# REALcontrol_boardv22.net
KiCad netlist of a schematic drawn in EAGLE
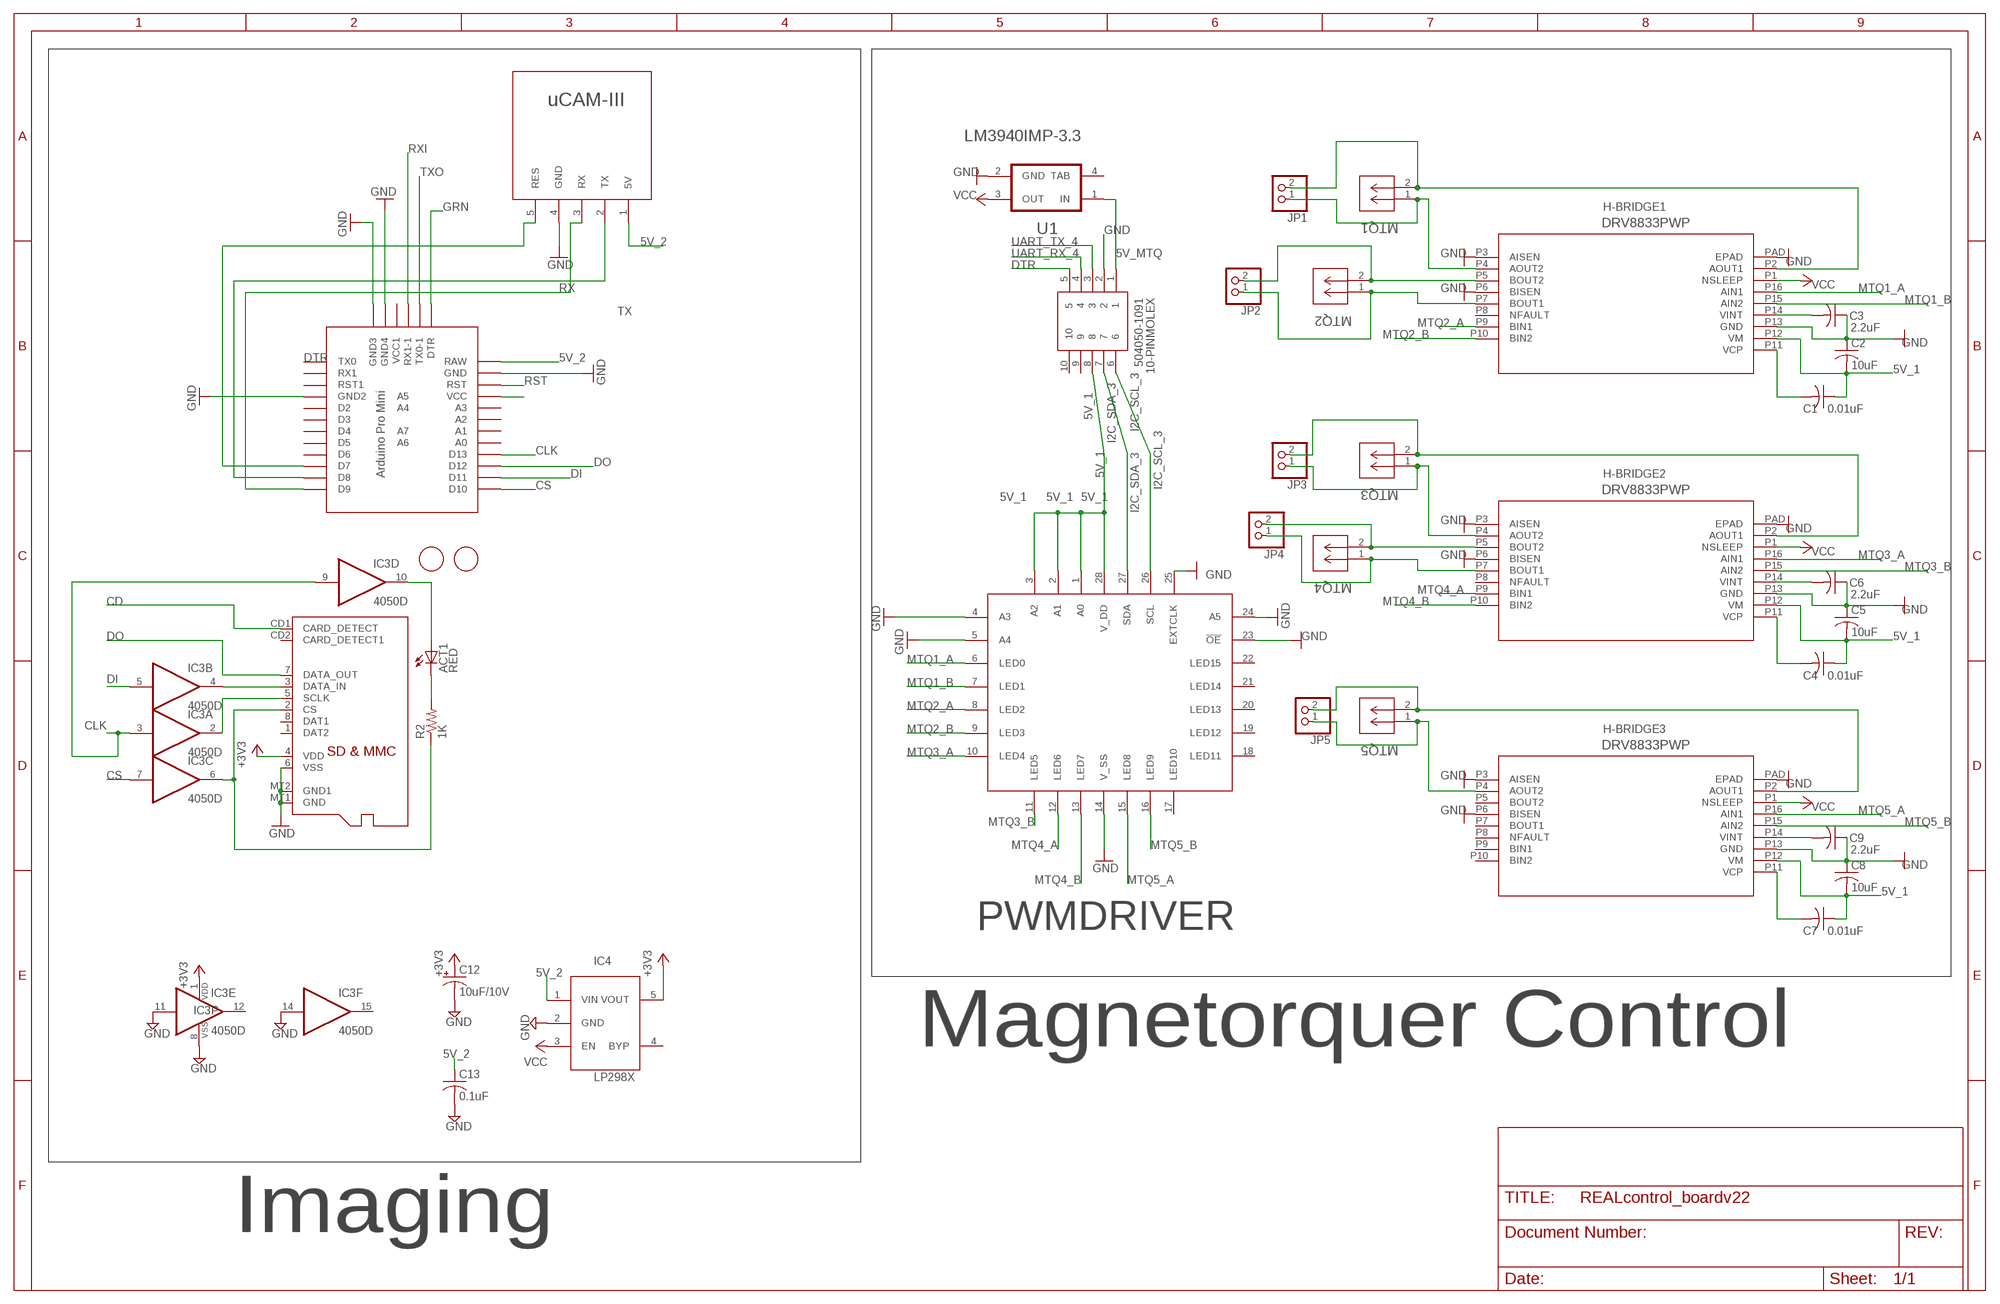
[diagram p0: schematic, sheet 1]

(export (version "E")
  (design (tool "Eeschema 10.0.6"))
  (components
    (comp (ref "10-PINMOLEX")
      (value "504050-1091")
      (footprint "eagle-import:504050-1091")
      (fields (field (name "MOUSER_PART_NUMBER") "538-504050-1091"))
      (libsource (lib "eagle-import") (part "504050-1091"))
    )
    (comp (ref "ACT1")
      (value "RED")
      (footprint "eagle-import:CHIP-LED0805")
      (libsource (lib "eagle-import") (part "LEDCHIP-LED0805"))
    )
    (comp (ref "C1")
      (value "0.01uF")
      (footprint "eagle-import:C0603K")
      (libsource (lib "eagle-import") (part "rcl_334_C-USC0603K"))
    )
    (comp (ref "C2")
      (value "10uF")
      (footprint "eagle-import:C1210K")
      (libsource (lib "eagle-import") (part "rcl_334_C-USC1210K"))
    )
    (comp (ref "C3")
      (value "2.2uF")
      (footprint "eagle-import:C0603K")
      (libsource (lib "eagle-import") (part "rcl_334_C-USC0603K"))
    )
    (comp (ref "C4")
      (value "0.01uF")
      (footprint "eagle-import:C0603K")
      (libsource (lib "eagle-import") (part "rcl_334_C-USC0603K"))
    )
    (comp (ref "C5")
      (value "10uF")
      (footprint "eagle-import:C1210K")
      (libsource (lib "eagle-import") (part "rcl_334_C-USC1210K"))
    )
    (comp (ref "C6")
      (value "2.2uF")
      (footprint "eagle-import:C0603K")
      (libsource (lib "eagle-import") (part "rcl_334_C-USC0603K"))
    )
    (comp (ref "C7")
      (value "0.01uF")
      (footprint "eagle-import:C0603K")
      (libsource (lib "eagle-import") (part "rcl_334_C-USC0603K"))
    )
    (comp (ref "C8")
      (value "10uF")
      (footprint "eagle-import:C1210K")
      (libsource (lib "eagle-import") (part "rcl_334_C-USC1210K"))
    )
    (comp (ref "C9")
      (value "2.2uF")
      (footprint "eagle-import:C0603K")
      (libsource (lib "eagle-import") (part "rcl_334_C-USC0603K"))
    )
    (comp (ref "C12")
      (value "10uF/10V")
      (footprint "eagle-import:A_3216-18R")
      (libsource (lib "eagle-import") (part "CPOL-USA/3216-18R"))
    )
    (comp (ref "C13")
      (value "0.1uF")
      (footprint "eagle-import:C0805K")
      (libsource (lib "eagle-import") (part "C-USC0805K"))
    )
    (comp (ref "H-BRIDGE1")
      (value "DRV8833PWP")
      (footprint "eagle-import:HTSSOP16")
      (libsource (lib "eagle-import") (part "DRV8833PWP"))
    )
    (comp (ref "H-BRIDGE2")
      (value "DRV8833PWP")
      (footprint "eagle-import:HTSSOP16")
      (libsource (lib "eagle-import") (part "DRV8833PWP"))
    )
    (comp (ref "H-BRIDGE3")
      (value "DRV8833PWP")
      (footprint "eagle-import:HTSSOP16")
      (libsource (lib "eagle-import") (part "DRV8833PWP"))
    )
    (comp (ref "IC3")
      (value "4050D")
      (footprint "eagle-import:SO16")
      (fields (field (name "OC_NEWARK") "unknown"))
      (libsource (lib "eagle-import") (part "4050D"))
    )
    (comp (ref "IC4")
      (value "LP298XS")
      (footprint "eagle-import:SOT23-5L")
      (libsource (lib "eagle-import") (part "LP298XS"))
    )
    (comp (ref "JP1")
      (value "PINHD-1X2")
      (footprint "eagle-import:1X02")
      (fields (field (name "MF") "MOLEX") (field (name "MPN") "22-11-2022"))
      (libsource (lib "eagle-import") (part "PINHD-1X2"))
    )
    (comp (ref "JP2")
      (value "PINHD-1X2")
      (footprint "eagle-import:1X02")
      (fields (field (name "MF") "MOLEX") (field (name "MPN") "22-11-2022"))
      (libsource (lib "eagle-import") (part "PINHD-1X2"))
    )
    (comp (ref "JP3")
      (value "PINHD-1X2")
      (footprint "eagle-import:1X02")
      (fields (field (name "MF") "MOLEX") (field (name "MPN") "22-11-2022"))
      (libsource (lib "eagle-import") (part "PINHD-1X2"))
    )
    (comp (ref "JP4")
      (value "PINHD-1X2")
      (footprint "eagle-import:1X02")
      (fields (field (name "MF") "MOLEX") (field (name "MPN") "22-11-2022"))
      (libsource (lib "eagle-import") (part "PINHD-1X2"))
    )
    (comp (ref "JP5")
      (value "PINHD-1X2")
      (footprint "eagle-import:1X02")
      (fields (field (name "MF") "MOLEX") (field (name "MPN") "22-11-2022"))
      (libsource (lib "eagle-import") (part "PINHD-1X2"))
    )
    (comp (ref "MTQ1")
      (value "DF13C-2P-1.25V(51)")
      (footprint "eagle-import:CON2_1X2_U_DF13")
      (libsource (lib "eagle-import") (part "DF13C-2P-1.25V(51)"))
    )
    (comp (ref "MTQ2")
      (value "DF13C-2P-1.25V(51)")
      (footprint "eagle-import:CON2_1X2_U_DF13")
      (libsource (lib "eagle-import") (part "DF13C-2P-1.25V(51)"))
    )
    (comp (ref "MTQ3")
      (value "DF13C-2P-1.25V(51)")
      (footprint "eagle-import:CON2_1X2_U_DF13")
      (libsource (lib "eagle-import") (part "DF13C-2P-1.25V(51)"))
    )
    (comp (ref "MTQ4")
      (value "DF13C-2P-1.25V(51)")
      (footprint "eagle-import:CON2_1X2_U_DF13")
      (libsource (lib "eagle-import") (part "DF13C-2P-1.25V(51)"))
    )
    (comp (ref "MTQ5")
      (value "DF13C-2P-1.25V(51)")
      (footprint "eagle-import:CON2_1X2_U_DF13")
      (libsource (lib "eagle-import") (part "DF13C-2P-1.25V(51)"))
    )
    (comp (ref "PWMDRIVER")
      (value "PCA9685PW")
      (footprint "eagle-import:TSSOP28")
      (libsource (lib "eagle-import") (part "PCA9685PW"))
    )
    (comp (ref "R2")
      (value "1K")
      (footprint "eagle-import:R0805")
      (libsource (lib "eagle-import") (part "R-US_R0805"))
    )
    (comp (ref "U$2")
      (value "UCAM-III")
      (footprint "eagle-import:UCAM-III")
      (libsource (lib "eagle-import") (part "UCAM-III"))
    )
    (comp (ref "U$6")
      (value "FIDUCIAL")
      (footprint "eagle-import:FIDUCIAL_1MM")
      (libsource (lib "eagle-import") (part "FIDUCIAL"))
    )
    (comp (ref "U$7")
      (value "FIDUCIAL")
      (footprint "eagle-import:FIDUCIAL_1MM")
      (libsource (lib "eagle-import") (part "FIDUCIAL"))
    )
    (comp (ref "U$8")
      (value "PRO-MINI-2")
      (footprint "eagle-import:PRO-MINI-2")
      (libsource (lib "eagle-import") (part "PRO-MINI-2"))
    )
    (comp (ref "U1")
      (value "TI_NATIONAL_SEMICONDUCTOR_LM3940IMP-3.3TI_NATIONAL_SEMICONDUCTOR_LM3940IMP-3.3_0_1")
      (footprint "eagle-import:TI_NATIONAL_SEMICONDUCTOR_LM3940IMP-3.3_1")
      (fields (field (name "MF") "TI National Semiconductor") (field (name "MPN") "LM3940IMP-3.3"))
      (libsource (lib "eagle-import") (part "TI_NATIONAL_SEMICONDUCTOR_LM3940IMP-3.3TI_NATIONAL_SEMICONDUCTOR_LM3940IMP-3.3_0_1"))
    )
    (comp (ref "X2")
      (value "MICROSD")
      (footprint "eagle-import:MICROSD")
      (libsource (lib "eagle-import") (part "MICROSD"))
    )
  )
  (nets
    (net (code "1") (name "+3V3") (class "Default")
      (node (ref "C12") (pin "+") (pinfunction "+_+") (pintype "passive"))
      (node (ref "IC3") (pin "1") (pinfunction "VDD_1") (pintype "power_in"))
      (node (ref "IC4") (pin "5") (pinfunction "VOUT_5") (pintype "bidirectional"))
      (node (ref "X2") (pin "4") (pinfunction "VDD_4") (pintype "power_in"))
    )
    (net (code "2") (name "/5V_1") (class "Default")
      (node (ref "10-PINMOLEX") (pin "8") (pinfunction "8_8") (pintype "bidirectional"))
      (node (ref "C1") (pin "1") (pinfunction "1_1") (pintype "passive"))
      (node (ref "C2") (pin "2") (pinfunction "2_2") (pintype "passive"))
      (node (ref "C4") (pin "1") (pinfunction "1_1") (pintype "passive"))
      (node (ref "C5") (pin "2") (pinfunction "2_2") (pintype "passive"))
      (node (ref "C7") (pin "1") (pinfunction "1_1") (pintype "passive"))
      (node (ref "C8") (pin "2") (pinfunction "2_2") (pintype "passive"))
      (node (ref "H-BRIDGE1") (pin "P12") (pinfunction "VM_P12") (pintype "power_in"))
      (node (ref "H-BRIDGE2") (pin "P12") (pinfunction "VM_P12") (pintype "power_in"))
      (node (ref "H-BRIDGE3") (pin "P12") (pinfunction "VM_P12") (pintype "power_in"))
      (node (ref "PWMDRIVER") (pin "1") (pinfunction "A0_1") (pintype "bidirectional"))
      (node (ref "PWMDRIVER") (pin "2") (pinfunction "A1_2") (pintype "bidirectional"))
      (node (ref "PWMDRIVER") (pin "28") (pinfunction "V_DD_28") (pintype "bidirectional"))
      (node (ref "PWMDRIVER") (pin "3") (pinfunction "A2_3") (pintype "bidirectional"))
    )
    (net (code "3") (name "/5V_2") (class "Default")
      (node (ref "C13") (pin "1") (pinfunction "1_1") (pintype "passive"))
      (node (ref "IC4") (pin "1") (pinfunction "VIN_1") (pintype "bidirectional"))
      (node (ref "U$2") (pin "1") (pinfunction "5V_1") (pintype "bidirectional"))
      (node (ref "U$8") (pin "RAW") (pinfunction "RAW_RAW") (pintype "bidirectional"))
    )
    (net (code "4") (name "/5V_MTQ") (class "Default")
      (node (ref "10-PINMOLEX") (pin "1") (pinfunction "1_1") (pintype "bidirectional"))
      (node (ref "U1") (pin "1") (pinfunction "IN_1") (pintype "power_in"))
    )
    (net (code "5") (name "/CD") (class "Default")
      (node (ref "X2") (pin "CD1") (pinfunction "CARD_DETECT_CD1") (pintype "passive"))
    )
    (net (code "6") (name "/CLK") (class "Default")
      (node (ref "IC3") (pin "3") (pinfunction "I_3") (pintype "input"))
      (node (ref "IC3") (pin "9") (pinfunction "I_9") (pintype "input"))
      (node (ref "U$8") (pin "D13") (pinfunction "D13_D13") (pintype "bidirectional"))
    )
    (net (code "7") (name "/CS") (class "Default")
      (node (ref "IC3") (pin "7") (pinfunction "I_7") (pintype "input"))
      (node (ref "U$8") (pin "D10") (pinfunction "D10_D10") (pintype "bidirectional"))
    )
    (net (code "8") (name "/DI") (class "Default")
      (node (ref "IC3") (pin "5") (pinfunction "I_5") (pintype "input"))
      (node (ref "U$8") (pin "D11") (pinfunction "D11_D11") (pintype "bidirectional"))
    )
    (net (code "9") (name "/DO") (class "Default")
      (node (ref "U$8") (pin "D12") (pinfunction "D12_D12") (pintype "bidirectional"))
      (node (ref "X2") (pin "7") (pinfunction "DATA_OUT_7") (pintype "output"))
    )
    (net (code "10") (name "/DTR") (class "Default")
      (node (ref "10-PINMOLEX") (pin "5") (pinfunction "5_5") (pintype "bidirectional"))
    )
    (net (code "11") (name "/GRN") (class "Default")
      (node (ref "U$8") (pin "DTR") (pinfunction "DTR_DTR") (pintype "bidirectional"))
    )
    (net (code "12") (name "/I2C_SCL_3") (class "Default")
      (node (ref "10-PINMOLEX") (pin "6") (pinfunction "6_6") (pintype "bidirectional"))
      (node (ref "PWMDRIVER") (pin "26") (pinfunction "SCL_26") (pintype "bidirectional"))
    )
    (net (code "13") (name "/I2C_SDA_3") (class "Default")
      (node (ref "10-PINMOLEX") (pin "7") (pinfunction "7_7") (pintype "bidirectional"))
      (node (ref "PWMDRIVER") (pin "27") (pinfunction "SDA_27") (pintype "bidirectional"))
    )
    (net (code "14") (name "/MTQ1_A") (class "Default")
      (node (ref "H-BRIDGE1") (pin "P16") (pinfunction "AIN1_P16") (pintype "input"))
      (node (ref "PWMDRIVER") (pin "6") (pinfunction "LED0_6") (pintype "bidirectional"))
    )
    (net (code "15") (name "/MTQ1_B") (class "Default")
      (node (ref "H-BRIDGE1") (pin "P15") (pinfunction "AIN2_P15") (pintype "input"))
      (node (ref "PWMDRIVER") (pin "7") (pinfunction "LED1_7") (pintype "bidirectional"))
    )
    (net (code "16") (name "/MTQ2_A") (class "Default")
      (node (ref "H-BRIDGE1") (pin "P9") (pinfunction "BIN1_P9") (pintype "input"))
      (node (ref "PWMDRIVER") (pin "8") (pinfunction "LED2_8") (pintype "bidirectional"))
    )
    (net (code "17") (name "/MTQ2_B") (class "Default")
      (node (ref "H-BRIDGE1") (pin "P10") (pinfunction "BIN2_P10") (pintype "input"))
      (node (ref "PWMDRIVER") (pin "9") (pinfunction "LED3_9") (pintype "bidirectional"))
    )
    (net (code "18") (name "/MTQ3_A") (class "Default")
      (node (ref "H-BRIDGE2") (pin "P16") (pinfunction "AIN1_P16") (pintype "input"))
      (node (ref "PWMDRIVER") (pin "10") (pinfunction "LED4_10") (pintype "bidirectional"))
    )
    (net (code "19") (name "/MTQ3_B") (class "Default")
      (node (ref "H-BRIDGE2") (pin "P15") (pinfunction "AIN2_P15") (pintype "input"))
      (node (ref "PWMDRIVER") (pin "11") (pinfunction "LED5_11") (pintype "bidirectional"))
    )
    (net (code "20") (name "/MTQ4_A") (class "Default")
      (node (ref "H-BRIDGE2") (pin "P9") (pinfunction "BIN1_P9") (pintype "input"))
      (node (ref "PWMDRIVER") (pin "12") (pinfunction "LED6_12") (pintype "bidirectional"))
    )
    (net (code "21") (name "/MTQ4_B") (class "Default")
      (node (ref "H-BRIDGE2") (pin "P10") (pinfunction "BIN2_P10") (pintype "input"))
      (node (ref "PWMDRIVER") (pin "13") (pinfunction "LED7_13") (pintype "bidirectional"))
    )
    (net (code "22") (name "/MTQ5_A") (class "Default")
      (node (ref "H-BRIDGE3") (pin "P16") (pinfunction "AIN1_P16") (pintype "input"))
      (node (ref "PWMDRIVER") (pin "15") (pinfunction "LED8_15") (pintype "bidirectional"))
    )
    (net (code "23") (name "/MTQ5_B") (class "Default")
      (node (ref "H-BRIDGE3") (pin "P15") (pinfunction "AIN2_P15") (pintype "input"))
      (node (ref "PWMDRIVER") (pin "16") (pinfunction "LED9_16") (pintype "bidirectional"))
    )
    (net (code "24") (name "/RST") (class "Default")
      (node (ref "U$8") (pin "RST") (pinfunction "RST_RST") (pintype "bidirectional"))
    )
    (net (code "25") (name "/RX") (class "Default")
      (node (ref "U$2") (pin "3") (pinfunction "RX_3") (pintype "bidirectional"))
      (node (ref "U$8") (pin "D9") (pinfunction "D9_D9") (pintype "bidirectional"))
    )
    (net (code "26") (name "/RXI") (class "Default")
      (node (ref "U$8") (pin "RX1-1") (pinfunction "RX1-1_RX1-1") (pintype "bidirectional"))
    )
    (net (code "27") (name "/TAB") (class "Default")
      (node (ref "U1") (pin "4") (pinfunction "TAB_4") (pintype "power_in"))
    )
    (net (code "28") (name "/TX") (class "Default")
      (node (ref "U$2") (pin "2") (pinfunction "TX_2") (pintype "bidirectional"))
      (node (ref "U$8") (pin "D8") (pinfunction "D8_D8") (pintype "bidirectional"))
    )
    (net (code "29") (name "/TXO") (class "Default")
      (node (ref "U$8") (pin "TX0-1") (pinfunction "TX0-1_TX0-1") (pintype "bidirectional"))
    )
    (net (code "30") (name "/UART_RX_4") (class "Default")
      (node (ref "10-PINMOLEX") (pin "4") (pinfunction "4_4") (pintype "bidirectional"))
    )
    (net (code "31") (name "/UART_TX_4") (class "Default")
      (node (ref "10-PINMOLEX") (pin "3") (pinfunction "3_3") (pintype "bidirectional"))
    )
    (net (code "32") (name "GND") (class "Default")
      (node (ref "10-PINMOLEX") (pin "2") (pinfunction "2_2") (pintype "bidirectional"))
      (node (ref "C12") (pin "-") (pinfunction "-_-") (pintype "passive"))
      (node (ref "C13") (pin "2") (pinfunction "2_2") (pintype "passive"))
      (node (ref "C2") (pin "1") (pinfunction "1_1") (pintype "passive"))
      (node (ref "C3") (pin "1") (pinfunction "1_1") (pintype "passive"))
      (node (ref "C5") (pin "1") (pinfunction "1_1") (pintype "passive"))
      (node (ref "C6") (pin "1") (pinfunction "1_1") (pintype "passive"))
      (node (ref "C8") (pin "1") (pinfunction "1_1") (pintype "passive"))
      (node (ref "C9") (pin "1") (pinfunction "1_1") (pintype "passive"))
      (node (ref "H-BRIDGE1") (pin "P13") (pinfunction "GND_P13") (pintype "power_in"))
      (node (ref "H-BRIDGE1") (pin "P3") (pinfunction "AISEN_P3") (pintype "bidirectional"))
      (node (ref "H-BRIDGE1") (pin "P6") (pinfunction "BISEN_P6") (pintype "bidirectional"))
      (node (ref "H-BRIDGE1") (pin "PAD") (pinfunction "EPAD_PAD") (pintype "passive"))
      (node (ref "H-BRIDGE2") (pin "P13") (pinfunction "GND_P13") (pintype "power_in"))
      (node (ref "H-BRIDGE2") (pin "P3") (pinfunction "AISEN_P3") (pintype "bidirectional"))
      (node (ref "H-BRIDGE2") (pin "P6") (pinfunction "BISEN_P6") (pintype "bidirectional"))
      (node (ref "H-BRIDGE2") (pin "PAD") (pinfunction "EPAD_PAD") (pintype "passive"))
      (node (ref "H-BRIDGE3") (pin "P13") (pinfunction "GND_P13") (pintype "power_in"))
      (node (ref "H-BRIDGE3") (pin "P3") (pinfunction "AISEN_P3") (pintype "bidirectional"))
      (node (ref "H-BRIDGE3") (pin "P6") (pinfunction "BISEN_P6") (pintype "bidirectional"))
      (node (ref "H-BRIDGE3") (pin "PAD") (pinfunction "EPAD_PAD") (pintype "passive"))
      (node (ref "IC3") (pin "11") (pinfunction "I_11") (pintype "input"))
      (node (ref "IC3") (pin "14") (pinfunction "I_14") (pintype "input"))
      (node (ref "IC3") (pin "8") (pinfunction "VSS_8") (pintype "power_in"))
      (node (ref "IC4") (pin "2") (pinfunction "GND_2") (pintype "bidirectional"))
      (node (ref "PWMDRIVER") (pin "14") (pinfunction "V_SS_14") (pintype "bidirectional"))
      (node (ref "PWMDRIVER") (pin "23") (pinfunction "~{OE}_23") (pintype "bidirectional"))
      (node (ref "PWMDRIVER") (pin "24") (pinfunction "A5_24") (pintype "bidirectional"))
      (node (ref "PWMDRIVER") (pin "25") (pinfunction "EXTCLK_25") (pintype "bidirectional"))
      (node (ref "PWMDRIVER") (pin "4") (pinfunction "A3_4") (pintype "bidirectional"))
      (node (ref "PWMDRIVER") (pin "5") (pinfunction "A4_5") (pintype "bidirectional"))
      (node (ref "U$2") (pin "4") (pinfunction "GND_4") (pintype "bidirectional"))
      (node (ref "U$8") (pin "GND") (pinfunction "GND_GND") (pintype "bidirectional"))
      (node (ref "U$8") (pin "GND1") (pinfunction "GND2_GND1") (pintype "bidirectional"))
      (node (ref "U$8") (pin "GND2") (pinfunction "GND3_GND2") (pintype "bidirectional"))
      (node (ref "U$8") (pin "GND3") (pinfunction "GND4_GND3") (pintype "bidirectional"))
      (node (ref "U1") (pin "2") (pinfunction "GND_2") (pintype "power_in"))
      (node (ref "X2") (pin "6") (pinfunction "VSS_6") (pintype "power_in"))
      (node (ref "X2") (pin "MT1") (pinfunction "GND_MT1") (pintype "power_in"))
      (node (ref "X2") (pin "MT2") (pinfunction "GND1_MT2") (pintype "power_in"))
    )
    (net (code "33") (name "Net-(ACT1-PadC)") (class "Default")
      (node (ref "ACT1") (pin "C") (pinfunction "C_C") (pintype "passive"))
      (node (ref "R2") (pin "2") (pinfunction "2_2") (pintype "passive"))
    )
    (net (code "34") (name "Net-(H-BRIDGE1-AOUT1)") (class "Default")
      (node (ref "H-BRIDGE1") (pin "P2") (pinfunction "AOUT1_P2") (pintype "output"))
      (node (ref "JP1") (pin "2") (pinfunction "2_2") (pintype "passive"))
      (node (ref "MTQ1") (pin "2") (pinfunction "2_2") (pintype "passive"))
    )
    (net (code "35") (name "Net-(H-BRIDGE1-AOUT2)") (class "Default")
      (node (ref "H-BRIDGE1") (pin "P4") (pinfunction "AOUT2_P4") (pintype "output"))
      (node (ref "JP1") (pin "1") (pinfunction "1_1") (pintype "passive"))
      (node (ref "MTQ1") (pin "1") (pinfunction "1_1") (pintype "passive"))
    )
    (net (code "36") (name "Net-(H-BRIDGE1-BOUT1)") (class "Default")
      (node (ref "H-BRIDGE1") (pin "P7") (pinfunction "BOUT1_P7") (pintype "output"))
      (node (ref "JP2") (pin "1") (pinfunction "1_1") (pintype "passive"))
      (node (ref "MTQ2") (pin "1") (pinfunction "1_1") (pintype "passive"))
    )
    (net (code "37") (name "Net-(H-BRIDGE1-BOUT2)") (class "Default")
      (node (ref "H-BRIDGE1") (pin "P5") (pinfunction "BOUT2_P5") (pintype "output"))
      (node (ref "JP2") (pin "2") (pinfunction "2_2") (pintype "passive"))
      (node (ref "MTQ2") (pin "2") (pinfunction "2_2") (pintype "passive"))
    )
    (net (code "38") (name "Net-(H-BRIDGE1-VCP)") (class "Default")
      (node (ref "C1") (pin "2") (pinfunction "2_2") (pintype "passive"))
      (node (ref "H-BRIDGE1") (pin "P11") (pinfunction "VCP_P11") (pintype "bidirectional"))
    )
    (net (code "39") (name "Net-(H-BRIDGE1-VINT)") (class "Default")
      (node (ref "C3") (pin "2") (pinfunction "2_2") (pintype "passive"))
      (node (ref "H-BRIDGE1") (pin "P14") (pinfunction "VINT_P14") (pintype "power_in"))
    )
    (net (code "40") (name "Net-(H-BRIDGE2-AOUT1)") (class "Default")
      (node (ref "H-BRIDGE2") (pin "P2") (pinfunction "AOUT1_P2") (pintype "output"))
      (node (ref "JP3") (pin "2") (pinfunction "2_2") (pintype "passive"))
      (node (ref "MTQ3") (pin "2") (pinfunction "2_2") (pintype "passive"))
    )
    (net (code "41") (name "Net-(H-BRIDGE2-AOUT2)") (class "Default")
      (node (ref "H-BRIDGE2") (pin "P4") (pinfunction "AOUT2_P4") (pintype "output"))
      (node (ref "JP3") (pin "1") (pinfunction "1_1") (pintype "passive"))
      (node (ref "MTQ3") (pin "1") (pinfunction "1_1") (pintype "passive"))
    )
    (net (code "42") (name "Net-(H-BRIDGE2-BOUT1)") (class "Default")
      (node (ref "H-BRIDGE2") (pin "P7") (pinfunction "BOUT1_P7") (pintype "output"))
      (node (ref "JP4") (pin "1") (pinfunction "1_1") (pintype "passive"))
      (node (ref "MTQ4") (pin "1") (pinfunction "1_1") (pintype "passive"))
    )
    (net (code "43") (name "Net-(H-BRIDGE2-BOUT2)") (class "Default")
      (node (ref "H-BRIDGE2") (pin "P5") (pinfunction "BOUT2_P5") (pintype "output"))
      (node (ref "JP4") (pin "2") (pinfunction "2_2") (pintype "passive"))
      (node (ref "MTQ4") (pin "2") (pinfunction "2_2") (pintype "passive"))
    )
    (net (code "44") (name "Net-(H-BRIDGE2-VCP)") (class "Default")
      (node (ref "C4") (pin "2") (pinfunction "2_2") (pintype "passive"))
      (node (ref "H-BRIDGE2") (pin "P11") (pinfunction "VCP_P11") (pintype "bidirectional"))
    )
    (net (code "45") (name "Net-(H-BRIDGE2-VINT)") (class "Default")
      (node (ref "C6") (pin "2") (pinfunction "2_2") (pintype "passive"))
      (node (ref "H-BRIDGE2") (pin "P14") (pinfunction "VINT_P14") (pintype "power_in"))
    )
    (net (code "46") (name "Net-(H-BRIDGE3-AOUT1)") (class "Default")
      (node (ref "H-BRIDGE3") (pin "P2") (pinfunction "AOUT1_P2") (pintype "output"))
      (node (ref "JP5") (pin "2") (pinfunction "2_2") (pintype "passive"))
      (node (ref "MTQ5") (pin "2") (pinfunction "2_2") (pintype "passive"))
    )
    (net (code "47") (name "Net-(H-BRIDGE3-AOUT2)") (class "Default")
      (node (ref "H-BRIDGE3") (pin "P4") (pinfunction "AOUT2_P4") (pintype "output"))
      (node (ref "JP5") (pin "1") (pinfunction "1_1") (pintype "passive"))
      (node (ref "MTQ5") (pin "1") (pinfunction "1_1") (pintype "passive"))
    )
    (net (code "48") (name "Net-(H-BRIDGE3-VCP)") (class "Default")
      (node (ref "C7") (pin "2") (pinfunction "2_2") (pintype "passive"))
      (node (ref "H-BRIDGE3") (pin "P11") (pinfunction "VCP_P11") (pintype "bidirectional"))
    )
    (net (code "49") (name "Net-(H-BRIDGE3-VINT)") (class "Default")
      (node (ref "C9") (pin "2") (pinfunction "2_2") (pintype "passive"))
      (node (ref "H-BRIDGE3") (pin "P14") (pinfunction "VINT_P14") (pintype "power_in"))
    )
    (net (code "50") (name "Net-(IC3A-O)") (class "Default")
      (node (ref "IC3") (pin "2") (pinfunction "O_2") (pintype "output"))
      (node (ref "X2") (pin "5") (pinfunction "SCLK_5") (pintype "input"))
    )
    (net (code "51") (name "Net-(IC3B-O)") (class "Default")
      (node (ref "IC3") (pin "4") (pinfunction "O_4") (pintype "output"))
      (node (ref "X2") (pin "3") (pinfunction "DATA_IN_3") (pintype "input"))
    )
    (net (code "52") (name "Net-(IC3C-O)") (class "Default")
      (node (ref "IC3") (pin "6") (pinfunction "O_6") (pintype "output"))
      (node (ref "R2") (pin "1") (pinfunction "1_1") (pintype "passive"))
      (node (ref "X2") (pin "2") (pinfunction "CS_2") (pintype "input"))
    )
    (net (code "53") (name "Net-(IC3D-O)") (class "Default")
      (node (ref "ACT1") (pin "A") (pinfunction "A_A") (pintype "passive"))
      (node (ref "IC3") (pin "10") (pinfunction "O_10") (pintype "output"))
    )
    (net (code "54") (name "Net-(U$2-RES)") (class "Default")
      (node (ref "U$2") (pin "5") (pinfunction "RES_5") (pintype "bidirectional"))
      (node (ref "U$8") (pin "D7") (pinfunction "D7_D7") (pintype "bidirectional"))
    )
    (net (code "55") (name "VCC") (class "Default")
      (node (ref "H-BRIDGE1") (pin "P1") (pinfunction "NSLEEP_P1") (pintype "input"))
      (node (ref "H-BRIDGE2") (pin "P1") (pinfunction "NSLEEP_P1") (pintype "input"))
      (node (ref "H-BRIDGE3") (pin "P1") (pinfunction "NSLEEP_P1") (pintype "input"))
      (node (ref "IC4") (pin "3") (pinfunction "EN_3") (pintype "bidirectional"))
      (node (ref "U1") (pin "3") (pinfunction "OUT_3") (pintype "power_in"))
    )
    (net (code "56") (name "unconnected-(10-PINMOLEX-Pad9)") (class "Default")
      (node (ref "10-PINMOLEX") (pin "9") (pinfunction "9_9") (pintype "bidirectional"))
    )
    (net (code "57") (name "unconnected-(10-PINMOLEX-Pad10)") (class "Default")
      (node (ref "10-PINMOLEX") (pin "10") (pinfunction "10_10") (pintype "bidirectional"))
    )
    (net (code "58") (name "unconnected-(H-BRIDGE1-NFAULT-PadP8)") (class "Default")
      (node (ref "H-BRIDGE1") (pin "P8") (pinfunction "NFAULT_P8") (pintype "output"))
    )
    (net (code "59") (name "unconnected-(H-BRIDGE2-NFAULT-PadP8)") (class "Default")
      (node (ref "H-BRIDGE2") (pin "P8") (pinfunction "NFAULT_P8") (pintype "output"))
    )
    (net (code "60") (name "unconnected-(H-BRIDGE3-BIN1-PadP9)") (class "Default")
      (node (ref "H-BRIDGE3") (pin "P9") (pinfunction "BIN1_P9") (pintype "input"))
    )
    (net (code "61") (name "unconnected-(H-BRIDGE3-BIN2-PadP10)") (class "Default")
      (node (ref "H-BRIDGE3") (pin "P10") (pinfunction "BIN2_P10") (pintype "input"))
    )
    (net (code "62") (name "unconnected-(H-BRIDGE3-BOUT1-PadP7)") (class "Default")
      (node (ref "H-BRIDGE3") (pin "P7") (pinfunction "BOUT1_P7") (pintype "output"))
    )
    (net (code "63") (name "unconnected-(H-BRIDGE3-BOUT2-PadP5)") (class "Default")
      (node (ref "H-BRIDGE3") (pin "P5") (pinfunction "BOUT2_P5") (pintype "output"))
    )
    (net (code "64") (name "unconnected-(H-BRIDGE3-NFAULT-PadP8)") (class "Default")
      (node (ref "H-BRIDGE3") (pin "P8") (pinfunction "NFAULT_P8") (pintype "output"))
    )
    (net (code "65") (name "unconnected-(IC3E-O-Pad12)") (class "Default")
      (node (ref "IC3") (pin "12") (pinfunction "O_12") (pintype "output"))
    )
    (net (code "66") (name "unconnected-(IC3F-O-Pad15)") (class "Default")
      (node (ref "IC3") (pin "15") (pinfunction "O_15") (pintype "output"))
    )
    (net (code "67") (name "unconnected-(IC4-BYP-Pad4)") (class "Default")
      (node (ref "IC4") (pin "4") (pinfunction "BYP_4") (pintype "bidirectional"))
    )
    (net (code "68") (name "unconnected-(PWMDRIVER-LED10-Pad17)") (class "Default")
      (node (ref "PWMDRIVER") (pin "17") (pinfunction "LED10_17") (pintype "bidirectional"))
    )
    (net (code "69") (name "unconnected-(PWMDRIVER-LED11-Pad18)") (class "Default")
      (node (ref "PWMDRIVER") (pin "18") (pinfunction "LED11_18") (pintype "bidirectional"))
    )
    (net (code "70") (name "unconnected-(PWMDRIVER-LED12-Pad19)") (class "Default")
      (node (ref "PWMDRIVER") (pin "19") (pinfunction "LED12_19") (pintype "bidirectional"))
    )
    (net (code "71") (name "unconnected-(PWMDRIVER-LED13-Pad20)") (class "Default")
      (node (ref "PWMDRIVER") (pin "20") (pinfunction "LED13_20") (pintype "bidirectional"))
    )
    (net (code "72") (name "unconnected-(PWMDRIVER-LED14-Pad21)") (class "Default")
      (node (ref "PWMDRIVER") (pin "21") (pinfunction "LED14_21") (pintype "bidirectional"))
    )
    (net (code "73") (name "unconnected-(PWMDRIVER-LED15-Pad22)") (class "Default")
      (node (ref "PWMDRIVER") (pin "22") (pinfunction "LED15_22") (pintype "bidirectional"))
    )
    (net (code "74") (name "unconnected-(U$8-PadA0)") (class "Default")
      (node (ref "U$8") (pin "A0") (pinfunction "A0_A0") (pintype "bidirectional"))
    )
    (net (code "75") (name "unconnected-(U$8-PadA1)") (class "Default")
      (node (ref "U$8") (pin "A1") (pinfunction "A1_A1") (pintype "bidirectional"))
    )
    (net (code "76") (name "unconnected-(U$8-PadA2)") (class "Default")
      (node (ref "U$8") (pin "A2") (pinfunction "A2_A2") (pintype "bidirectional"))
    )
    (net (code "77") (name "unconnected-(U$8-PadA3)") (class "Default")
      (node (ref "U$8") (pin "A3") (pinfunction "A3_A3") (pintype "bidirectional"))
    )
    (net (code "78") (name "unconnected-(U$8-PadA4)") (class "Default")
      (node (ref "U$8") (pin "A4") (pinfunction "A4_A4") (pintype "bidirectional"))
    )
    (net (code "79") (name "unconnected-(U$8-PadA5)") (class "Default")
      (node (ref "U$8") (pin "A5") (pinfunction "A5_A5") (pintype "bidirectional"))
    )
    (net (code "80") (name "unconnected-(U$8-PadA6)") (class "Default")
      (node (ref "U$8") (pin "A6") (pinfunction "A6_A6") (pintype "bidirectional"))
    )
    (net (code "81") (name "unconnected-(U$8-PadA7)") (class "Default")
      (node (ref "U$8") (pin "A7") (pinfunction "A7_A7") (pintype "bidirectional"))
    )
    (net (code "82") (name "unconnected-(U$8-PadD2)") (class "Default")
      (node (ref "U$8") (pin "D2") (pinfunction "D2_D2") (pintype "bidirectional"))
    )
    (net (code "83") (name "unconnected-(U$8-PadD3)") (class "Default")
      (node (ref "U$8") (pin "D3") (pinfunction "D3_D3") (pintype "bidirectional"))
    )
    (net (code "84") (name "unconnected-(U$8-PadD4)") (class "Default")
      (node (ref "U$8") (pin "D4") (pinfunction "D4_D4") (pintype "bidirectional"))
    )
    (net (code "85") (name "unconnected-(U$8-PadD5)") (class "Default")
      (node (ref "U$8") (pin "D5") (pinfunction "D5_D5") (pintype "bidirectional"))
    )
    (net (code "86") (name "unconnected-(U$8-PadD6)") (class "Default")
      (node (ref "U$8") (pin "D6") (pinfunction "D6_D6") (pintype "bidirectional"))
    )
    (net (code "87") (name "unconnected-(U$8-PadRST1)") (class "Default")
      (node (ref "U$8") (pin "RST1") (pinfunction "RST1_RST1") (pintype "bidirectional"))
    )
    (net (code "88") (name "unconnected-(U$8-PadRX1)") (class "Default")
      (node (ref "U$8") (pin "RX1") (pinfunction "RX1_RX1") (pintype "bidirectional"))
    )
    (net (code "89") (name "unconnected-(U$8-PadTX0)") (class "Default")
      (node (ref "U$8") (pin "TX0") (pinfunction "TX0_TX0") (pintype "bidirectional"))
    )
    (net (code "90") (name "unconnected-(U$8-PadVCC)") (class "Default")
      (node (ref "U$8") (pin "VCC") (pinfunction "VCC_VCC") (pintype "bidirectional"))
    )
    (net (code "91") (name "unconnected-(U$8-PadVCC1)") (class "Default")
      (node (ref "U$8") (pin "VCC1") (pinfunction "VCC1_VCC1") (pintype "bidirectional"))
    )
    (net (code "92") (name "unconnected-(X2-CARD_DETECT1-PadCD2)") (class "Default")
      (node (ref "X2") (pin "CD2") (pinfunction "CARD_DETECT1_CD2") (pintype "passive"))
    )
    (net (code "93") (name "unconnected-(X2-DAT1-Pad8)") (class "Default")
      (node (ref "X2") (pin "8") (pinfunction "DAT1_8") (pintype "bidirectional"))
    )
    (net (code "94") (name "unconnected-(X2-DAT2-Pad1)") (class "Default")
      (node (ref "X2") (pin "1") (pinfunction "DAT2_1") (pintype "bidirectional"))
    )
  )
)
